# Teensy_board.net
KiCad netlist of a schematic drawn in EAGLE
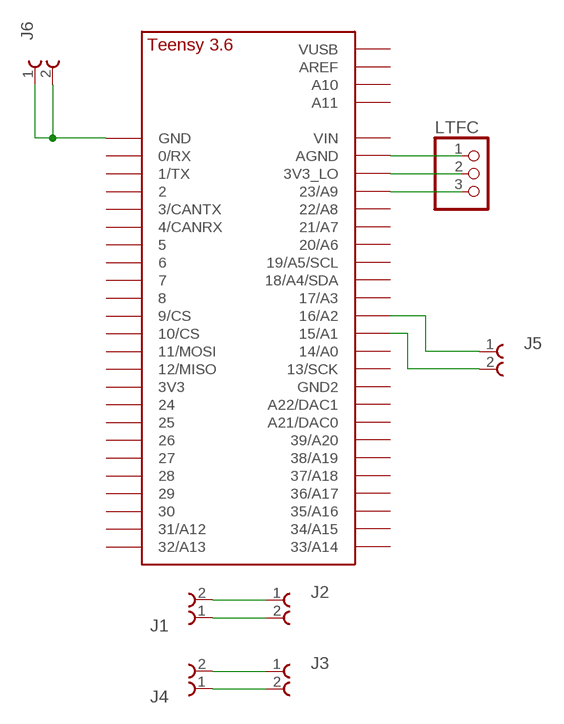
[diagram p0: schematic, sheet 1]

(export (version "E")
  (design (tool "Eeschema 10.0.6"))
  (components
    (comp (ref "J1")
      (value "691103110002")
      (footprint "eagle-import:691103110002")
      (libsource (lib "eagle-import") (part "691103110002"))
    )
    (comp (ref "J2")
      (value "691103110002")
      (footprint "eagle-import:691103110002")
      (libsource (lib "eagle-import") (part "691103110002"))
    )
    (comp (ref "J3")
      (value "691103110002")
      (footprint "eagle-import:691103110002")
      (libsource (lib "eagle-import") (part "691103110002"))
    )
    (comp (ref "J4")
      (value "691103110002")
      (footprint "eagle-import:691103110002")
      (libsource (lib "eagle-import") (part "691103110002"))
    )
    (comp (ref "J5")
      (value "691103110002")
      (footprint "eagle-import:691103110002")
      (libsource (lib "eagle-import") (part "691103110002"))
    )
    (comp (ref "J6")
      (value "691103110002")
      (footprint "eagle-import:691103110002")
      (libsource (lib "eagle-import") (part "691103110002"))
    )
    (comp (ref "LTFC")
      (value "PINHD-1X3")
      (footprint "eagle-import:1X03")
      (libsource (lib "eagle-import") (part "PINHD-1X3"))
    )
    (comp (ref "U$1")
      (value "TEENSY_3.5/3.6_BASIC")
      (footprint "eagle-import:TEENSY_3.5_3.6_BASIC")
      (libsource (lib "eagle-import") (part "TEENSY_3.5/3.6_BASIC"))
    )
  )
  (nets
    (net (code "1") (name "Net-(J1-Pad1)") (class "Default")
      (node (ref "J1") (pin "1") (pinfunction "1_1") (pintype "passive"))
      (node (ref "J2") (pin "2") (pinfunction "2_2") (pintype "passive"))
    )
    (net (code "2") (name "Net-(J1-Pad2)") (class "Default")
      (node (ref "J1") (pin "2") (pinfunction "2_2") (pintype "passive"))
      (node (ref "J2") (pin "1") (pinfunction "1_1") (pintype "passive"))
    )
    (net (code "3") (name "Net-(J3-Pad1)") (class "Default")
      (node (ref "J3") (pin "1") (pinfunction "1_1") (pintype "passive"))
      (node (ref "J4") (pin "2") (pinfunction "2_2") (pintype "passive"))
    )
    (net (code "4") (name "Net-(J3-Pad2)") (class "Default")
      (node (ref "J3") (pin "2") (pinfunction "2_2") (pintype "passive"))
      (node (ref "J4") (pin "1") (pinfunction "1_1") (pintype "passive"))
    )
    (net (code "5") (name "Net-(J5-Pad1)") (class "Default")
      (node (ref "J5") (pin "1") (pinfunction "1_1") (pintype "passive"))
      (node (ref "U$1") (pin "16/A2") (pinfunction "16/A2_16/A2") (pintype "bidirectional"))
    )
    (net (code "6") (name "Net-(J5-Pad2)") (class "Default")
      (node (ref "J5") (pin "2") (pinfunction "2_2") (pintype "passive"))
      (node (ref "U$1") (pin "15/A1") (pinfunction "15/A1_15/A1") (pintype "bidirectional"))
    )
    (net (code "7") (name "Net-(J6-Pad1)") (class "Default")
      (node (ref "J6") (pin "1") (pinfunction "1_1") (pintype "passive"))
      (node (ref "J6") (pin "2") (pinfunction "2_2") (pintype "passive"))
      (node (ref "U$1") (pin "GND") (pinfunction "GND_GND") (pintype "bidirectional"))
    )
    (net (code "8") (name "Net-(LTFC-Pad1)") (class "Default")
      (node (ref "LTFC") (pin "1") (pinfunction "1_1") (pintype "passive"))
      (node (ref "U$1") (pin "AGND") (pinfunction "AGND_AGND") (pintype "bidirectional"))
    )
    (net (code "9") (name "Net-(LTFC-Pad2)") (class "Default")
      (node (ref "LTFC") (pin "2") (pinfunction "2_2") (pintype "passive"))
      (node (ref "U$1") (pin "3V3_LO") (pinfunction "3V3_LO_3V3_LO") (pintype "bidirectional"))
    )
    (net (code "10") (name "Net-(LTFC-Pad3)") (class "Default")
      (node (ref "LTFC") (pin "3") (pinfunction "3_3") (pintype "passive"))
      (node (ref "U$1") (pin "23/A9") (pinfunction "23/A9_23/A9") (pintype "bidirectional"))
    )
    (net (code "11") (name "unconnected-(U$1-A21{slash}DAC0-Pad21{slash}DAC0)") (class "Default")
      (node (ref "U$1") (pin "21/DAC0") (pinfunction "A21/DAC0_21/DAC0") (pintype "bidirectional"))
    )
    (net (code "12") (name "unconnected-(U$1-Pad0{slash}RX)") (class "Default")
      (node (ref "U$1") (pin "0/RX") (pinfunction "0/RX_0/RX") (pintype "bidirectional"))
    )
    (net (code "13") (name "unconnected-(U$1-Pad1{slash}TX)") (class "Default")
      (node (ref "U$1") (pin "1/TX") (pinfunction "1/TX_1/TX") (pintype "bidirectional"))
    )
    (net (code "14") (name "unconnected-(U$1-Pad2)") (class "Default")
      (node (ref "U$1") (pin "2") (pinfunction "2_2") (pintype "bidirectional"))
    )
    (net (code "15") (name "unconnected-(U$1-Pad3V3)") (class "Default")
      (node (ref "U$1") (pin "3V3") (pinfunction "3V3_3V3") (pintype "bidirectional"))
    )
    (net (code "16") (name "unconnected-(U$1-Pad3{slash}CANTX)") (class "Default")
      (node (ref "U$1") (pin "3/CANTX") (pinfunction "3/CANTX_3/CANTX") (pintype "bidirectional"))
    )
    (net (code "17") (name "unconnected-(U$1-Pad4{slash}CANRX)") (class "Default")
      (node (ref "U$1") (pin "4/CANRX") (pinfunction "4/CANRX_4/CANRX") (pintype "bidirectional"))
    )
    (net (code "18") (name "unconnected-(U$1-Pad5)") (class "Default")
      (node (ref "U$1") (pin "5") (pinfunction "5_5") (pintype "bidirectional"))
    )
    (net (code "19") (name "unconnected-(U$1-Pad6)") (class "Default")
      (node (ref "U$1") (pin "6") (pinfunction "6_6") (pintype "bidirectional"))
    )
    (net (code "20") (name "unconnected-(U$1-Pad7)") (class "Default")
      (node (ref "U$1") (pin "7") (pinfunction "7_7") (pintype "bidirectional"))
    )
    (net (code "21") (name "unconnected-(U$1-Pad8)") (class "Default")
      (node (ref "U$1") (pin "8") (pinfunction "8_8") (pintype "bidirectional"))
    )
    (net (code "22") (name "unconnected-(U$1-Pad9{slash}CS)") (class "Default")
      (node (ref "U$1") (pin "9/CS") (pinfunction "9/CS_9/CS") (pintype "bidirectional"))
    )
    (net (code "23") (name "unconnected-(U$1-Pad10{slash}CS)") (class "Default")
      (node (ref "U$1") (pin "10/CS") (pinfunction "10/CS_10/CS") (pintype "bidirectional"))
    )
    (net (code "24") (name "unconnected-(U$1-Pad11{slash}MOSI)") (class "Default")
      (node (ref "U$1") (pin "11/MOSI") (pinfunction "11/MOSI_11/MOSI") (pintype "bidirectional"))
    )
    (net (code "25") (name "unconnected-(U$1-Pad12{slash}MISO)") (class "Default")
      (node (ref "U$1") (pin "12/MISO") (pinfunction "12/MISO_12/MISO") (pintype "bidirectional"))
    )
    (net (code "26") (name "unconnected-(U$1-Pad13{slash}SCK)") (class "Default")
      (node (ref "U$1") (pin "13/SCK") (pinfunction "13/SCK_13/SCK") (pintype "bidirectional"))
    )
    (net (code "27") (name "unconnected-(U$1-Pad14{slash}A0)") (class "Default")
      (node (ref "U$1") (pin "14/A0") (pinfunction "14/A0_14/A0") (pintype "bidirectional"))
    )
    (net (code "28") (name "unconnected-(U$1-Pad17{slash}A3)") (class "Default")
      (node (ref "U$1") (pin "17/A3") (pinfunction "17/A3_17/A3") (pintype "bidirectional"))
    )
    (net (code "29") (name "unconnected-(U$1-Pad18{slash}A4{slash}SDA)") (class "Default")
      (node (ref "U$1") (pin "18/A4/SDA") (pinfunction "18/A4/SDA_18/A4/SDA") (pintype "bidirectional"))
    )
    (net (code "30") (name "unconnected-(U$1-Pad19{slash}A5{slash}SCL)") (class "Default")
      (node (ref "U$1") (pin "19/A5/SCL") (pinfunction "19/A5/SCL_19/A5/SCL") (pintype "bidirectional"))
    )
    (net (code "31") (name "unconnected-(U$1-Pad20{slash}A6)") (class "Default")
      (node (ref "U$1") (pin "20/A6") (pinfunction "20/A6_20/A6") (pintype "bidirectional"))
    )
    (net (code "32") (name "unconnected-(U$1-Pad21{slash}A7)") (class "Default")
      (node (ref "U$1") (pin "21/A7") (pinfunction "21/A7_21/A7") (pintype "bidirectional"))
    )
    (net (code "33") (name "unconnected-(U$1-Pad22{slash}A8)") (class "Default")
      (node (ref "U$1") (pin "22/A8") (pinfunction "22/A8_22/A8") (pintype "bidirectional"))
    )
    (net (code "34") (name "unconnected-(U$1-Pad24)") (class "Default")
      (node (ref "U$1") (pin "24") (pinfunction "24_24") (pintype "bidirectional"))
    )
    (net (code "35") (name "unconnected-(U$1-Pad25)") (class "Default")
      (node (ref "U$1") (pin "25") (pinfunction "25_25") (pintype "bidirectional"))
    )
    (net (code "36") (name "unconnected-(U$1-Pad26)") (class "Default")
      (node (ref "U$1") (pin "26") (pinfunction "26_26") (pintype "bidirectional"))
    )
    (net (code "37") (name "unconnected-(U$1-Pad27)") (class "Default")
      (node (ref "U$1") (pin "27") (pinfunction "27_27") (pintype "bidirectional"))
    )
    (net (code "38") (name "unconnected-(U$1-Pad28)") (class "Default")
      (node (ref "U$1") (pin "28") (pinfunction "28_28") (pintype "bidirectional"))
    )
    (net (code "39") (name "unconnected-(U$1-Pad29)") (class "Default")
      (node (ref "U$1") (pin "29") (pinfunction "29_29") (pintype "bidirectional"))
    )
    (net (code "40") (name "unconnected-(U$1-Pad30)") (class "Default")
      (node (ref "U$1") (pin "30") (pinfunction "30_30") (pintype "bidirectional"))
    )
    (net (code "41") (name "unconnected-(U$1-Pad31{slash}A12)") (class "Default")
      (node (ref "U$1") (pin "31/A12") (pinfunction "31/A12_31/A12") (pintype "bidirectional"))
    )
    (net (code "42") (name "unconnected-(U$1-Pad32{slash}A13)") (class "Default")
      (node (ref "U$1") (pin "32/A13") (pinfunction "32/A13_32/A13") (pintype "bidirectional"))
    )
    (net (code "43") (name "unconnected-(U$1-Pad33{slash}A14)") (class "Default")
      (node (ref "U$1") (pin "33/A14") (pinfunction "33/A14_33/A14") (pintype "bidirectional"))
    )
    (net (code "44") (name "unconnected-(U$1-Pad34{slash}A15)") (class "Default")
      (node (ref "U$1") (pin "34/A15") (pinfunction "34/A15_34/A15") (pintype "bidirectional"))
    )
    (net (code "45") (name "unconnected-(U$1-Pad35{slash}A16)") (class "Default")
      (node (ref "U$1") (pin "35/A16") (pinfunction "35/A16_35/A16") (pintype "bidirectional"))
    )
    (net (code "46") (name "unconnected-(U$1-Pad36{slash}A17)") (class "Default")
      (node (ref "U$1") (pin "36/A17") (pinfunction "36/A17_36/A17") (pintype "bidirectional"))
    )
    (net (code "47") (name "unconnected-(U$1-Pad37{slash}A18)") (class "Default")
      (node (ref "U$1") (pin "37/A18") (pinfunction "37/A18_37/A18") (pintype "bidirectional"))
    )
    (net (code "48") (name "unconnected-(U$1-Pad38{slash}A19)") (class "Default")
      (node (ref "U$1") (pin "38/A19") (pinfunction "38/A19_38/A19") (pintype "bidirectional"))
    )
    (net (code "49") (name "unconnected-(U$1-Pad39{slash}A20)") (class "Default")
      (node (ref "U$1") (pin "39/A20") (pinfunction "39/A20_39/A20") (pintype "bidirectional"))
    )
    (net (code "50") (name "unconnected-(U$1-PadA10)") (class "Default")
      (node (ref "U$1") (pin "A10") (pinfunction "A10_A10") (pintype "bidirectional"))
    )
    (net (code "51") (name "unconnected-(U$1-PadA11)") (class "Default")
      (node (ref "U$1") (pin "A11") (pinfunction "A11_A11") (pintype "bidirectional"))
    )
    (net (code "52") (name "unconnected-(U$1-PadA22{slash}DAC1)") (class "Default")
      (node (ref "U$1") (pin "A22/DAC1") (pinfunction "A22/DAC1_A22/DAC1") (pintype "bidirectional"))
    )
    (net (code "53") (name "unconnected-(U$1-PadAREF)") (class "Default")
      (node (ref "U$1") (pin "AREF") (pinfunction "AREF_AREF") (pintype "bidirectional"))
    )
    (net (code "54") (name "unconnected-(U$1-PadGND2)") (class "Default")
      (node (ref "U$1") (pin "GND2") (pinfunction "GND2_GND2") (pintype "bidirectional"))
    )
    (net (code "55") (name "unconnected-(U$1-PadVIN)") (class "Default")
      (node (ref "U$1") (pin "VIN") (pinfunction "VIN_VIN") (pintype "bidirectional"))
    )
    (net (code "56") (name "unconnected-(U$1-PadVUSB)") (class "Default")
      (node (ref "U$1") (pin "VUSB") (pinfunction "VUSB_VUSB") (pintype "bidirectional"))
    )
  )
)
